# Connector_EEM.net
KiCad netlist of a schematic drawn in Altium Designer
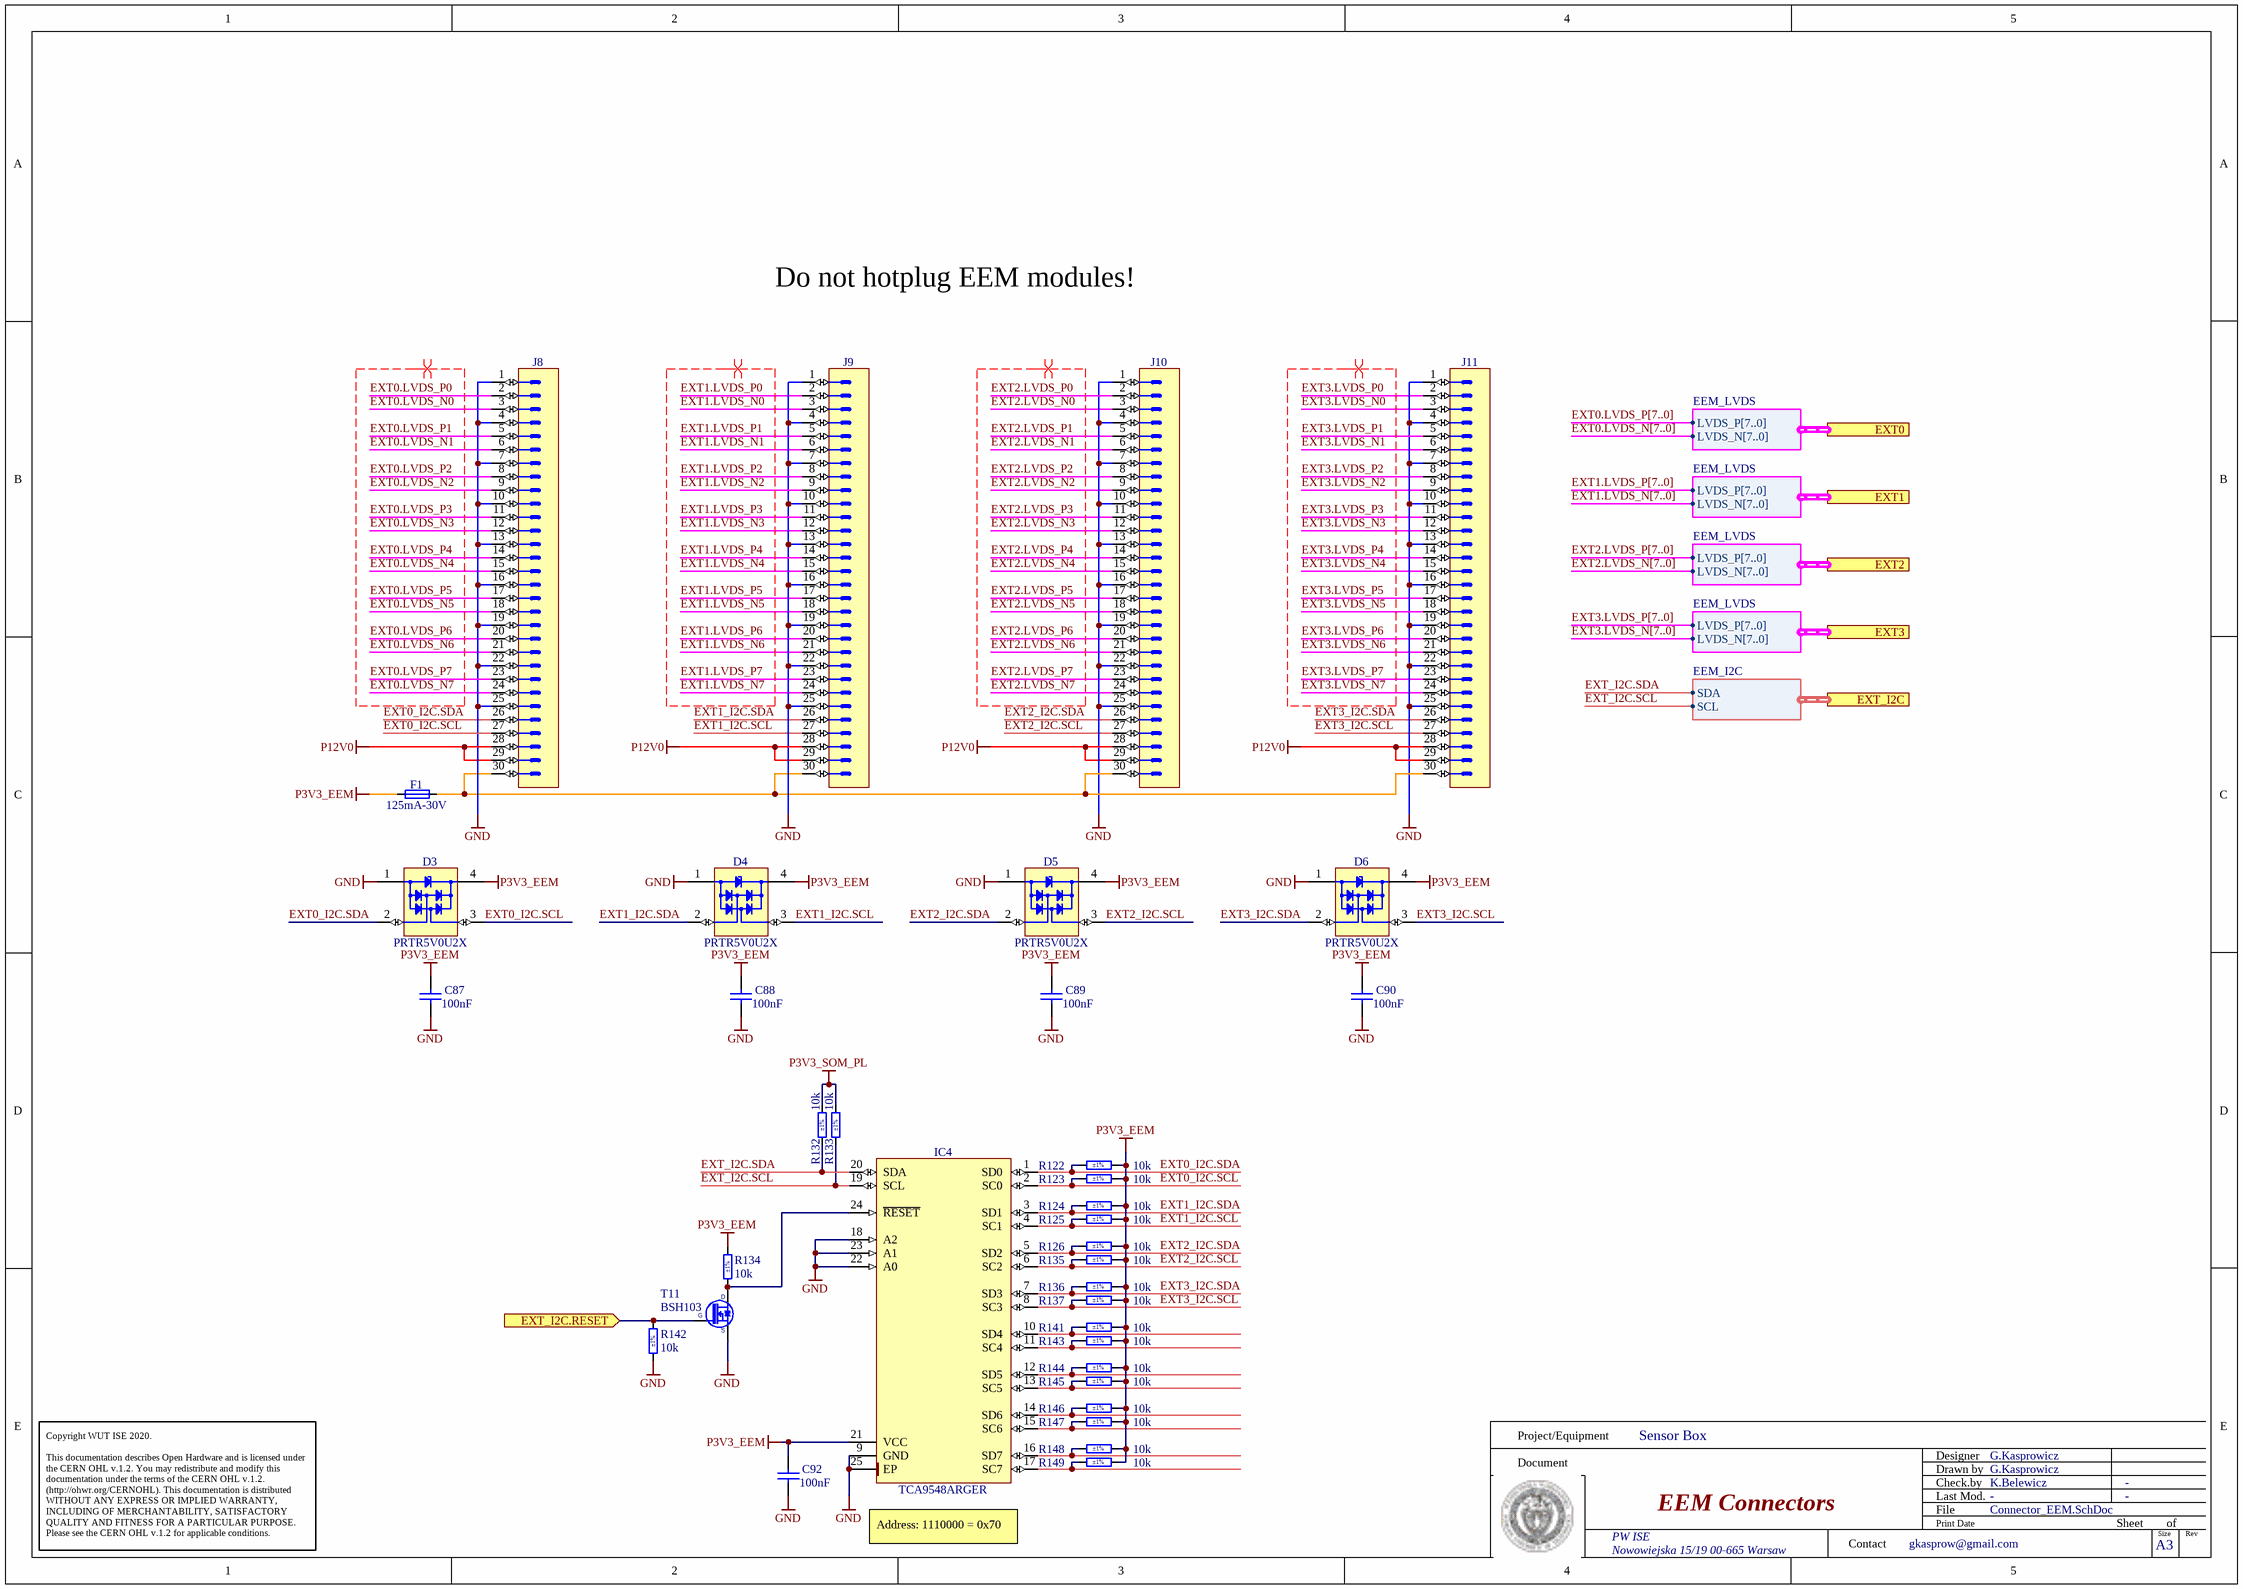
[diagram p0: Connector_EEM.SchDoc]

(export (version "E")
  (design (tool "Eeschema 10.0.6"))
  (components
    (comp (ref "C87")
      (value "100nF")
      (footprint "CAPC1005X55N")
      (description "Non-polarised capacitor")
      (fields
        (field (name "PART NUMBER") "CC0402_100NF_16V_10%_X5R")
        (field (name "VOLTAGE") "16V")
        (field (name "AUTHOR") "CERN DEM JLC")
      )
      (libsource (lib "Capacitors") (part "Capacitor - non polarized"))
    )
    (comp (ref "C88")
      (value "100nF")
      (footprint "CAPC1005X55N")
      (description "Non-polarised capacitor")
      (fields
        (field (name "PART NUMBER") "CC0402_100NF_16V_10%_X5R")
        (field (name "VOLTAGE") "16V")
        (field (name "AUTHOR") "CERN DEM JLC")
      )
      (libsource (lib "Capacitors") (part "Capacitor - non polarized"))
    )
    (comp (ref "C89")
      (value "100nF")
      (footprint "CAPC1005X55N")
      (description "Non-polarised capacitor")
      (fields
        (field (name "PART NUMBER") "CC0402_100NF_16V_10%_X5R")
        (field (name "VOLTAGE") "16V")
        (field (name "AUTHOR") "CERN DEM JLC")
      )
      (libsource (lib "Capacitors") (part "Capacitor - non polarized"))
    )
    (comp (ref "C90")
      (value "100nF")
      (footprint "CAPC1005X55N")
      (description "Non-polarised capacitor")
      (fields
        (field (name "PART NUMBER") "CC0402_100NF_16V_10%_X5R")
        (field (name "VOLTAGE") "16V")
        (field (name "AUTHOR") "CERN DEM JLC")
      )
      (libsource (lib "Capacitors") (part "Capacitor - non polarized"))
    )
    (comp (ref "C92")
      (value "100nF")
      (footprint "CAPC1005X55N")
      (description "Non-polarised capacitor")
      (fields
        (field (name "PART NUMBER") "CC0402_100NF_16V_10%_X5R")
        (field (name "VOLTAGE") "16V")
        (field (name "AUTHOR") "CERN DEM JLC")
      )
      (libsource (lib "Capacitors") (part "Capacitor - non polarized"))
    )
    (comp (ref "D3")
      (value "PRTR5V0U2X")
      (footprint "SOT190P230X110-4N")
      (description "Ultra Low Capacitance Double Rail-to-Rail ESD Protection Diode")
      (fields
        (field (name "VOLTAGE") "5.5V")
        (field (name "MANUFACTURER") "NXP SEMICONDUCTORS")
        (field (name "AUTHOR") "CERN DEM JLC")
      )
      (libsource (lib "ICs And Semiconductors") (part "PRTR5V0U2X"))
    )
    (comp (ref "D4")
      (value "PRTR5V0U2X")
      (footprint "SOT190P230X110-4N")
      (description "Ultra Low Capacitance Double Rail-to-Rail ESD Protection Diode")
      (fields
        (field (name "VOLTAGE") "5.5V")
        (field (name "MANUFACTURER") "NXP SEMICONDUCTORS")
        (field (name "AUTHOR") "CERN DEM JLC")
      )
      (libsource (lib "ICs And Semiconductors") (part "PRTR5V0U2X"))
    )
    (comp (ref "D5")
      (value "PRTR5V0U2X")
      (footprint "SOT190P230X110-4N")
      (description "Ultra Low Capacitance Double Rail-to-Rail ESD Protection Diode")
      (fields
        (field (name "VOLTAGE") "5.5V")
        (field (name "MANUFACTURER") "NXP SEMICONDUCTORS")
        (field (name "AUTHOR") "CERN DEM JLC")
      )
      (libsource (lib "ICs And Semiconductors") (part "PRTR5V0U2X"))
    )
    (comp (ref "D6")
      (value "PRTR5V0U2X")
      (footprint "SOT190P230X110-4N")
      (description "Ultra Low Capacitance Double Rail-to-Rail ESD Protection Diode")
      (fields
        (field (name "VOLTAGE") "5.5V")
        (field (name "MANUFACTURER") "NXP SEMICONDUCTORS")
        (field (name "AUTHOR") "CERN DEM JLC")
      )
      (libsource (lib "ICs And Semiconductors") (part "PRTR5V0U2X"))
    )
    (comp (ref "F1")
      (value "125mA-30V")
      (footprint "FUSR_LITTELFUSE_1206L012")
      (description "Fuse")
      (fields
        (field (name "PART NUMBER") "FUSR_LITTELFUSE_1206L012")
        (field (name "MANUFACTURER") "LITTELFUSE")
        (field (name "AUTHOR") "CERN DEM JLC")
      )
      (libsource (lib "Eletro-mechanical") (part "Fuse"))
    )
    (comp (ref "IC4")
      (value "TCA9548ARGER")
      (footprint "QFN50P400X400X100-25N-S220")
      (description "Low Voltage 8-Channel I2C Switch With Reset")
      (fields (field (name "MANUFACTURER") "TEXAS INSTRUMENTS") (field (name "AUTHOR") "CERN DEM JLC"))
      (libsource (lib "ICs And Semiconductors") (part "TCA9548ARGER"))
    )
    (comp (ref "J8")
      (value "~")
      (footprint "3M_N2530-6002RB")
      (description "Connector 30 Male")
      (fields
        (field (name "PART NUMBER") "3M_N2530-6002RB")
        (field (name "MANUFACTURER") "3M")
        (field (name "AUTHOR") "CERN DEM JLC")
      )
      (libsource (lib "Connectors") (part "Connector 30 Male"))
    )
    (comp (ref "J9")
      (value "~")
      (footprint "3M_N2530-6002RB")
      (description "Connector 30 Male")
      (fields
        (field (name "PART NUMBER") "3M_N2530-6002RB")
        (field (name "MANUFACTURER") "3M")
        (field (name "AUTHOR") "CERN DEM JLC")
      )
      (libsource (lib "Connectors") (part "Connector 30 Male"))
    )
    (comp (ref "J10")
      (value "~")
      (footprint "3M_N2530-6002RB")
      (description "Connector 30 Male")
      (fields
        (field (name "PART NUMBER") "3M_N2530-6002RB")
        (field (name "MANUFACTURER") "3M")
        (field (name "AUTHOR") "CERN DEM JLC")
      )
      (libsource (lib "Connectors") (part "Connector 30 Male"))
    )
    (comp (ref "J11")
      (value "~")
      (footprint "3M_N2530-6002RB")
      (description "Connector 30 Male")
      (fields
        (field (name "PART NUMBER") "3M_N2530-6002RB")
        (field (name "MANUFACTURER") "3M")
        (field (name "AUTHOR") "CERN DEM JLC")
      )
      (libsource (lib "Connectors") (part "Connector 30 Male"))
    )
    (comp (ref "R122")
      (value "10k")
      (footprint "RESC1005X40N")
      (description "Resistor - 1%")
      (fields
        (field (name "TOLERANCE") "±1%")
        (field (name "PART NUMBER") "R0402_10K_1%_0.0625W_100PPM")
        (field (name "POWER") "0.0625W")
        (field (name "AUTHOR") "CERN DEM JLC")
      )
      (libsource (lib "Resistors") (part "Resistor - 1%"))
    )
    (comp (ref "R123")
      (value "10k")
      (footprint "RESC1005X40N")
      (description "Resistor - 1%")
      (fields
        (field (name "TOLERANCE") "±1%")
        (field (name "PART NUMBER") "R0402_10K_1%_0.0625W_100PPM")
        (field (name "POWER") "0.0625W")
        (field (name "AUTHOR") "CERN DEM JLC")
      )
      (libsource (lib "Resistors") (part "Resistor - 1%"))
    )
    (comp (ref "R124")
      (value "10k")
      (footprint "RESC1005X40N")
      (description "Resistor - 1%")
      (fields
        (field (name "TOLERANCE") "±1%")
        (field (name "PART NUMBER") "R0402_10K_1%_0.0625W_100PPM")
        (field (name "POWER") "0.0625W")
        (field (name "AUTHOR") "CERN DEM JLC")
      )
      (libsource (lib "Resistors") (part "Resistor - 1%"))
    )
    (comp (ref "R125")
      (value "10k")
      (footprint "RESC1005X40N")
      (description "Resistor - 1%")
      (fields
        (field (name "TOLERANCE") "±1%")
        (field (name "PART NUMBER") "R0402_10K_1%_0.0625W_100PPM")
        (field (name "POWER") "0.0625W")
        (field (name "AUTHOR") "CERN DEM JLC")
      )
      (libsource (lib "Resistors") (part "Resistor - 1%"))
    )
    (comp (ref "R126")
      (value "10k")
      (footprint "RESC1005X40N")
      (description "Resistor - 1%")
      (fields
        (field (name "TOLERANCE") "±1%")
        (field (name "PART NUMBER") "R0402_10K_1%_0.0625W_100PPM")
        (field (name "POWER") "0.0625W")
        (field (name "AUTHOR") "CERN DEM JLC")
      )
      (libsource (lib "Resistors") (part "Resistor - 1%"))
    )
    (comp (ref "R132")
      (value "10k")
      (footprint "RESC1005X40N")
      (description "Resistor - 1%")
      (fields
        (field (name "TOLERANCE") "±1%")
        (field (name "PART NUMBER") "R0402_10K_1%_0.0625W_100PPM")
        (field (name "POWER") "0.0625W")
        (field (name "AUTHOR") "CERN DEM JLC")
      )
      (libsource (lib "Resistors") (part "Resistor - 1%"))
    )
    (comp (ref "R133")
      (value "10k")
      (footprint "RESC1005X40N")
      (description "Resistor - 1%")
      (fields
        (field (name "TOLERANCE") "±1%")
        (field (name "PART NUMBER") "R0402_10K_1%_0.0625W_100PPM")
        (field (name "POWER") "0.0625W")
        (field (name "AUTHOR") "CERN DEM JLC")
      )
      (libsource (lib "Resistors") (part "Resistor - 1%"))
    )
    (comp (ref "R134")
      (value "10k")
      (footprint "RESC1005X40N")
      (description "Resistor - 1%")
      (fields
        (field (name "TOLERANCE") "±1%")
        (field (name "PART NUMBER") "R0402_10K_1%_0.0625W_100PPM")
        (field (name "POWER") "0.0625W")
        (field (name "AUTHOR") "CERN DEM JLC")
      )
      (libsource (lib "Resistors") (part "Resistor - 1%"))
    )
    (comp (ref "R135")
      (value "10k")
      (footprint "RESC1005X40N")
      (description "Resistor - 1%")
      (fields
        (field (name "TOLERANCE") "±1%")
        (field (name "PART NUMBER") "R0402_10K_1%_0.0625W_100PPM")
        (field (name "POWER") "0.0625W")
        (field (name "AUTHOR") "CERN DEM JLC")
      )
      (libsource (lib "Resistors") (part "Resistor - 1%"))
    )
    (comp (ref "R136")
      (value "10k")
      (footprint "RESC1005X40N")
      (description "Resistor - 1%")
      (fields
        (field (name "TOLERANCE") "±1%")
        (field (name "PART NUMBER") "R0402_10K_1%_0.0625W_100PPM")
        (field (name "POWER") "0.0625W")
        (field (name "AUTHOR") "CERN DEM JLC")
      )
      (libsource (lib "Resistors") (part "Resistor - 1%"))
    )
    (comp (ref "R137")
      (value "10k")
      (footprint "RESC1005X40N")
      (description "Resistor - 1%")
      (fields
        (field (name "TOLERANCE") "±1%")
        (field (name "PART NUMBER") "R0402_10K_1%_0.0625W_100PPM")
        (field (name "POWER") "0.0625W")
        (field (name "AUTHOR") "CERN DEM JLC")
      )
      (libsource (lib "Resistors") (part "Resistor - 1%"))
    )
    (comp (ref "R141")
      (value "10k")
      (footprint "RESC1005X40N")
      (description "Resistor - 1%")
      (fields
        (field (name "TOLERANCE") "±1%")
        (field (name "PART NUMBER") "R0402_10K_1%_0.0625W_100PPM")
        (field (name "POWER") "0.0625W")
        (field (name "AUTHOR") "CERN DEM JLC")
      )
      (libsource (lib "Resistors") (part "Resistor - 1%"))
    )
    (comp (ref "R142")
      (value "10k")
      (footprint "RESC1005X40N")
      (description "Resistor - 1%")
      (fields
        (field (name "TOLERANCE") "±1%")
        (field (name "PART NUMBER") "R0402_10K_1%_0.0625W_100PPM")
        (field (name "POWER") "0.0625W")
        (field (name "AUTHOR") "CERN DEM JLC")
      )
      (libsource (lib "Resistors") (part "Resistor - 1%"))
    )
    (comp (ref "R143")
      (value "10k")
      (footprint "RESC1005X40N")
      (description "Resistor - 1%")
      (fields
        (field (name "TOLERANCE") "±1%")
        (field (name "PART NUMBER") "R0402_10K_1%_0.0625W_100PPM")
        (field (name "POWER") "0.0625W")
        (field (name "AUTHOR") "CERN DEM JLC")
      )
      (libsource (lib "Resistors") (part "Resistor - 1%"))
    )
    (comp (ref "R144")
      (value "10k")
      (footprint "RESC1005X40N")
      (description "Resistor - 1%")
      (fields
        (field (name "TOLERANCE") "±1%")
        (field (name "PART NUMBER") "R0402_10K_1%_0.0625W_100PPM")
        (field (name "POWER") "0.0625W")
        (field (name "AUTHOR") "CERN DEM JLC")
      )
      (libsource (lib "Resistors") (part "Resistor - 1%"))
    )
    (comp (ref "R145")
      (value "10k")
      (footprint "RESC1005X40N")
      (description "Resistor - 1%")
      (fields
        (field (name "TOLERANCE") "±1%")
        (field (name "PART NUMBER") "R0402_10K_1%_0.0625W_100PPM")
        (field (name "POWER") "0.0625W")
        (field (name "AUTHOR") "CERN DEM JLC")
      )
      (libsource (lib "Resistors") (part "Resistor - 1%"))
    )
    (comp (ref "R146")
      (value "10k")
      (footprint "RESC1005X40N")
      (description "Resistor - 1%")
      (fields
        (field (name "TOLERANCE") "±1%")
        (field (name "PART NUMBER") "R0402_10K_1%_0.0625W_100PPM")
        (field (name "POWER") "0.0625W")
        (field (name "AUTHOR") "CERN DEM JLC")
      )
      (libsource (lib "Resistors") (part "Resistor - 1%"))
    )
    (comp (ref "R147")
      (value "10k")
      (footprint "RESC1005X40N")
      (description "Resistor - 1%")
      (fields
        (field (name "TOLERANCE") "±1%")
        (field (name "PART NUMBER") "R0402_10K_1%_0.0625W_100PPM")
        (field (name "POWER") "0.0625W")
        (field (name "AUTHOR") "CERN DEM JLC")
      )
      (libsource (lib "Resistors") (part "Resistor - 1%"))
    )
    (comp (ref "R148")
      (value "10k")
      (footprint "RESC1005X40N")
      (description "Resistor - 1%")
      (fields
        (field (name "TOLERANCE") "±1%")
        (field (name "PART NUMBER") "R0402_10K_1%_0.0625W_100PPM")
        (field (name "POWER") "0.0625W")
        (field (name "AUTHOR") "CERN DEM JLC")
      )
      (libsource (lib "Resistors") (part "Resistor - 1%"))
    )
    (comp (ref "R149")
      (value "10k")
      (footprint "RESC1005X40N")
      (description "Resistor - 1%")
      (fields
        (field (name "TOLERANCE") "±1%")
        (field (name "PART NUMBER") "R0402_10K_1%_0.0625W_100PPM")
        (field (name "POWER") "0.0625W")
        (field (name "AUTHOR") "CERN DEM JLC")
      )
      (libsource (lib "Resistors") (part "Resistor - 1%"))
    )
    (comp (ref "T11")
      (value "BSH103")
      (footprint "SOT95P230X110-3N")
      (description "N-CHANNEL MOSFET WITH DIODE")
      (fields (field (name "MANUFACTURER") "NEXPERIA") (field (name "AUTHOR") "CERN DEM JLC"))
      (libsource (lib "ICs And Semiconductors") (part "N-MOSFET-D 1G 2S 3D"))
    )
  )
  (nets
    (net (code "3") (name "/EXT0.LVDS_N0") (class "Default")
      (node (ref "J8") (pin "3") (pinfunction "3_3") (pintype "bidirectional"))
    )
    (net (code "4") (name "/EXT0.LVDS_N1") (class "Default")
      (node (ref "J8") (pin "6") (pinfunction "6_6") (pintype "bidirectional"))
    )
    (net (code "5") (name "/EXT0.LVDS_N2") (class "Default")
      (node (ref "J8") (pin "9") (pinfunction "9_9") (pintype "bidirectional"))
    )
    (net (code "6") (name "/EXT0.LVDS_N3") (class "Default")
      (node (ref "J8") (pin "12") (pinfunction "12_12") (pintype "bidirectional"))
    )
    (net (code "7") (name "/EXT0.LVDS_N4") (class "Default")
      (node (ref "J8") (pin "15") (pinfunction "15_15") (pintype "bidirectional"))
    )
    (net (code "8") (name "/EXT0.LVDS_N5") (class "Default")
      (node (ref "J8") (pin "18") (pinfunction "18_18") (pintype "bidirectional"))
    )
    (net (code "9") (name "/EXT0.LVDS_N6") (class "Default")
      (node (ref "J8") (pin "21") (pinfunction "21_21") (pintype "bidirectional"))
    )
    (net (code "10") (name "/EXT0.LVDS_N7") (class "Default")
      (node (ref "J8") (pin "24") (pinfunction "24_24") (pintype "bidirectional"))
    )
    (net (code "12") (name "/EXT0.LVDS_P0") (class "Default")
      (node (ref "J8") (pin "2") (pinfunction "2_2") (pintype "bidirectional"))
    )
    (net (code "13") (name "/EXT0.LVDS_P1") (class "Default")
      (node (ref "J8") (pin "5") (pinfunction "5_5") (pintype "bidirectional"))
    )
    (net (code "14") (name "/EXT0.LVDS_P2") (class "Default")
      (node (ref "J8") (pin "8") (pinfunction "8_8") (pintype "bidirectional"))
    )
    (net (code "15") (name "/EXT0.LVDS_P3") (class "Default")
      (node (ref "J8") (pin "11") (pinfunction "11_11") (pintype "bidirectional"))
    )
    (net (code "16") (name "/EXT0.LVDS_P4") (class "Default")
      (node (ref "J8") (pin "14") (pinfunction "14_14") (pintype "bidirectional"))
    )
    (net (code "17") (name "/EXT0.LVDS_P5") (class "Default")
      (node (ref "J8") (pin "17") (pinfunction "17_17") (pintype "bidirectional"))
    )
    (net (code "18") (name "/EXT0.LVDS_P6") (class "Default")
      (node (ref "J8") (pin "20") (pinfunction "20_20") (pintype "bidirectional"))
    )
    (net (code "19") (name "/EXT0.LVDS_P7") (class "Default")
      (node (ref "J8") (pin "23") (pinfunction "23_23") (pintype "bidirectional"))
    )
    (net (code "21") (name "/EXT0_I2C.SCL") (class "Default")
      (node (ref "D3") (pin "3") (pinfunction "I/O2_3") (pintype "bidirectional"))
      (node (ref "IC4") (pin "2") (pinfunction "SC0_2") (pintype "bidirectional"))
      (node (ref "J8") (pin "27") (pinfunction "27_27") (pintype "bidirectional"))
      (node (ref "R123") (pin "1") (pinfunction "1_1") (pintype "passive"))
    )
    (net (code "22") (name "/EXT0_I2C.SDA") (class "Default")
      (node (ref "D3") (pin "2") (pinfunction "I/O1_2") (pintype "bidirectional"))
      (node (ref "IC4") (pin "1") (pinfunction "SD0_1") (pintype "bidirectional"))
      (node (ref "J8") (pin "26") (pinfunction "26_26") (pintype "bidirectional"))
      (node (ref "R122") (pin "1") (pinfunction "1_1") (pintype "passive"))
    )
    (net (code "23") (name "/EXT1.LVDS_N0") (class "Default")
      (node (ref "J9") (pin "3") (pinfunction "3_3") (pintype "bidirectional"))
    )
    (net (code "24") (name "/EXT1.LVDS_N1") (class "Default")
      (node (ref "J9") (pin "6") (pinfunction "6_6") (pintype "bidirectional"))
    )
    (net (code "25") (name "/EXT1.LVDS_N2") (class "Default")
      (node (ref "J9") (pin "9") (pinfunction "9_9") (pintype "bidirectional"))
    )
    (net (code "26") (name "/EXT1.LVDS_N3") (class "Default")
      (node (ref "J9") (pin "12") (pinfunction "12_12") (pintype "bidirectional"))
    )
    (net (code "27") (name "/EXT1.LVDS_N4") (class "Default")
      (node (ref "J9") (pin "15") (pinfunction "15_15") (pintype "bidirectional"))
    )
    (net (code "28") (name "/EXT1.LVDS_N5") (class "Default")
      (node (ref "J9") (pin "18") (pinfunction "18_18") (pintype "bidirectional"))
    )
    (net (code "29") (name "/EXT1.LVDS_N6") (class "Default")
      (node (ref "J9") (pin "21") (pinfunction "21_21") (pintype "bidirectional"))
    )
    (net (code "30") (name "/EXT1.LVDS_N7") (class "Default")
      (node (ref "J9") (pin "24") (pinfunction "24_24") (pintype "bidirectional"))
    )
    (net (code "32") (name "/EXT1.LVDS_P0") (class "Default")
      (node (ref "J9") (pin "2") (pinfunction "2_2") (pintype "bidirectional"))
    )
    (net (code "33") (name "/EXT1.LVDS_P1") (class "Default")
      (node (ref "J9") (pin "5") (pinfunction "5_5") (pintype "bidirectional"))
    )
    (net (code "34") (name "/EXT1.LVDS_P2") (class "Default")
      (node (ref "J9") (pin "8") (pinfunction "8_8") (pintype "bidirectional"))
    )
    (net (code "35") (name "/EXT1.LVDS_P3") (class "Default")
      (node (ref "J9") (pin "11") (pinfunction "11_11") (pintype "bidirectional"))
    )
    (net (code "36") (name "/EXT1.LVDS_P4") (class "Default")
      (node (ref "J9") (pin "14") (pinfunction "14_14") (pintype "bidirectional"))
    )
    (net (code "37") (name "/EXT1.LVDS_P5") (class "Default")
      (node (ref "J9") (pin "17") (pinfunction "17_17") (pintype "bidirectional"))
    )
    (net (code "38") (name "/EXT1.LVDS_P6") (class "Default")
      (node (ref "J9") (pin "20") (pinfunction "20_20") (pintype "bidirectional"))
    )
    (net (code "39") (name "/EXT1.LVDS_P7") (class "Default")
      (node (ref "J9") (pin "23") (pinfunction "23_23") (pintype "bidirectional"))
    )
    (net (code "41") (name "/EXT1_I2C.SCL") (class "Default")
      (node (ref "D4") (pin "3") (pinfunction "I/O2_3") (pintype "bidirectional"))
      (node (ref "IC4") (pin "4") (pinfunction "SC1_4") (pintype "bidirectional"))
      (node (ref "J9") (pin "27") (pinfunction "27_27") (pintype "bidirectional"))
      (node (ref "R125") (pin "1") (pinfunction "1_1") (pintype "passive"))
    )
    (net (code "42") (name "/EXT1_I2C.SDA") (class "Default")
      (node (ref "D4") (pin "2") (pinfunction "I/O1_2") (pintype "bidirectional"))
      (node (ref "IC4") (pin "3") (pinfunction "SD1_3") (pintype "bidirectional"))
      (node (ref "J9") (pin "26") (pinfunction "26_26") (pintype "bidirectional"))
      (node (ref "R124") (pin "1") (pinfunction "1_1") (pintype "passive"))
    )
    (net (code "43") (name "/EXT2.LVDS_N0") (class "Default")
      (node (ref "J10") (pin "3") (pinfunction "3_3") (pintype "bidirectional"))
    )
    (net (code "44") (name "/EXT2.LVDS_N1") (class "Default")
      (node (ref "J10") (pin "6") (pinfunction "6_6") (pintype "bidirectional"))
    )
    (net (code "45") (name "/EXT2.LVDS_N2") (class "Default")
      (node (ref "J10") (pin "9") (pinfunction "9_9") (pintype "bidirectional"))
    )
    (net (code "46") (name "/EXT2.LVDS_N3") (class "Default")
      (node (ref "J10") (pin "12") (pinfunction "12_12") (pintype "bidirectional"))
    )
    (net (code "47") (name "/EXT2.LVDS_N4") (class "Default")
      (node (ref "J10") (pin "15") (pinfunction "15_15") (pintype "bidirectional"))
    )
    (net (code "48") (name "/EXT2.LVDS_N5") (class "Default")
      (node (ref "J10") (pin "18") (pinfunction "18_18") (pintype "bidirectional"))
    )
    (net (code "49") (name "/EXT2.LVDS_N6") (class "Default")
      (node (ref "J10") (pin "21") (pinfunction "21_21") (pintype "bidirectional"))
    )
    (net (code "50") (name "/EXT2.LVDS_N7") (class "Default")
      (node (ref "J10") (pin "24") (pinfunction "24_24") (pintype "bidirectional"))
    )
    (net (code "52") (name "/EXT2.LVDS_P0") (class "Default")
      (node (ref "J10") (pin "2") (pinfunction "2_2") (pintype "bidirectional"))
    )
    (net (code "53") (name "/EXT2.LVDS_P1") (class "Default")
      (node (ref "J10") (pin "5") (pinfunction "5_5") (pintype "bidirectional"))
    )
    (net (code "54") (name "/EXT2.LVDS_P2") (class "Default")
      (node (ref "J10") (pin "8") (pinfunction "8_8") (pintype "bidirectional"))
    )
    (net (code "55") (name "/EXT2.LVDS_P3") (class "Default")
      (node (ref "J10") (pin "11") (pinfunction "11_11") (pintype "bidirectional"))
    )
    (net (code "56") (name "/EXT2.LVDS_P4") (class "Default")
      (node (ref "J10") (pin "14") (pinfunction "14_14") (pintype "bidirectional"))
    )
    (net (code "57") (name "/EXT2.LVDS_P5") (class "Default")
      (node (ref "J10") (pin "17") (pinfunction "17_17") (pintype "bidirectional"))
    )
    (net (code "58") (name "/EXT2.LVDS_P6") (class "Default")
      (node (ref "J10") (pin "20") (pinfunction "20_20") (pintype "bidirectional"))
    )
    (net (code "59") (name "/EXT2.LVDS_P7") (class "Default")
      (node (ref "J10") (pin "23") (pinfunction "23_23") (pintype "bidirectional"))
    )
    (net (code "61") (name "/EXT2_I2C.SCL") (class "Default")
      (node (ref "D5") (pin "3") (pinfunction "I/O2_3") (pintype "bidirectional"))
      (node (ref "IC4") (pin "6") (pinfunction "SC2_6") (pintype "bidirectional"))
      (node (ref "J10") (pin "27") (pinfunction "27_27") (pintype "bidirectional"))
      (node (ref "R135") (pin "1") (pinfunction "1_1") (pintype "passive"))
    )
    (net (code "62") (name "/EXT2_I2C.SDA") (class "Default")
      (node (ref "D5") (pin "2") (pinfunction "I/O1_2") (pintype "bidirectional"))
      (node (ref "IC4") (pin "5") (pinfunction "SD2_5") (pintype "bidirectional"))
      (node (ref "J10") (pin "26") (pinfunction "26_26") (pintype "bidirectional"))
      (node (ref "R126") (pin "1") (pinfunction "1_1") (pintype "passive"))
    )
    (net (code "63") (name "/EXT3.LVDS_N0") (class "Default")
      (node (ref "J11") (pin "3") (pinfunction "3_3") (pintype "bidirectional"))
    )
    (net (code "64") (name "/EXT3.LVDS_N1") (class "Default")
      (node (ref "J11") (pin "6") (pinfunction "6_6") (pintype "bidirectional"))
    )
    (net (code "65") (name "/EXT3.LVDS_N2") (class "Default")
      (node (ref "J11") (pin "9") (pinfunction "9_9") (pintype "bidirectional"))
    )
    (net (code "66") (name "/EXT3.LVDS_N3") (class "Default")
      (node (ref "J11") (pin "12") (pinfunction "12_12") (pintype "bidirectional"))
    )
    (net (code "67") (name "/EXT3.LVDS_N4") (class "Default")
      (node (ref "J11") (pin "15") (pinfunction "15_15") (pintype "bidirectional"))
    )
    (net (code "68") (name "/EXT3.LVDS_N5") (class "Default")
      (node (ref "J11") (pin "18") (pinfunction "18_18") (pintype "bidirectional"))
    )
    (net (code "69") (name "/EXT3.LVDS_N6") (class "Default")
      (node (ref "J11") (pin "21") (pinfunction "21_21") (pintype "bidirectional"))
    )
    (net (code "70") (name "/EXT3.LVDS_N7") (class "Default")
      (node (ref "J11") (pin "24") (pinfunction "24_24") (pintype "bidirectional"))
    )
    (net (code "72") (name "/EXT3.LVDS_P0") (class "Default")
      (node (ref "J11") (pin "2") (pinfunction "2_2") (pintype "bidirectional"))
    )
    (net (code "73") (name "/EXT3.LVDS_P1") (class "Default")
      (node (ref "J11") (pin "5") (pinfunction "5_5") (pintype "bidirectional"))
    )
    (net (code "74") (name "/EXT3.LVDS_P2") (class "Default")
      (node (ref "J11") (pin "8") (pinfunction "8_8") (pintype "bidirectional"))
    )
    (net (code "75") (name "/EXT3.LVDS_P3") (class "Default")
      (node (ref "J11") (pin "11") (pinfunction "11_11") (pintype "bidirectional"))
    )
    (net (code "76") (name "/EXT3.LVDS_P4") (class "Default")
      (node (ref "J11") (pin "14") (pinfunction "14_14") (pintype "bidirectional"))
    )
    (net (code "77") (name "/EXT3.LVDS_P5") (class "Default")
      (node (ref "J11") (pin "17") (pinfunction "17_17") (pintype "bidirectional"))
    )
    (net (code "78") (name "/EXT3.LVDS_P6") (class "Default")
      (node (ref "J11") (pin "20") (pinfunction "20_20") (pintype "bidirectional"))
    )
    (net (code "79") (name "/EXT3.LVDS_P7") (class "Default")
      (node (ref "J11") (pin "23") (pinfunction "23_23") (pintype "bidirectional"))
    )
    (net (code "81") (name "/EXT3_I2C.SCL") (class "Default")
      (node (ref "D6") (pin "3") (pinfunction "I/O2_3") (pintype "bidirectional"))
      (node (ref "IC4") (pin "8") (pinfunction "SC3_8") (pintype "bidirectional"))
      (node (ref "J11") (pin "27") (pinfunction "27_27") (pintype "bidirectional"))
      (node (ref "R137") (pin "1") (pinfunction "1_1") (pintype "passive"))
    )
    (net (code "82") (name "/EXT3_I2C.SDA") (class "Default")
      (node (ref "D6") (pin "2") (pinfunction "I/O1_2") (pintype "bidirectional"))
      (node (ref "IC4") (pin "7") (pinfunction "SD3_7") (pintype "bidirectional"))
      (node (ref "J11") (pin "26") (pinfunction "26_26") (pintype "bidirectional"))
      (node (ref "R136") (pin "1") (pinfunction "1_1") (pintype "passive"))
    )
    (net (code "83") (name "/EXT_I2C.RESET") (class "Default")
      (node (ref "R142") (pin "2") (pinfunction "2_2") (pintype "passive"))
      (node (ref "T11") (pin "1") (pinfunction "G_1") (pintype "passive"))
    )
    (net (code "84") (name "/EXT_I2C.SCL") (class "Default")
      (node (ref "IC4") (pin "19") (pinfunction "SCL_19") (pintype "bidirectional"))
      (node (ref "R133") (pin "1") (pinfunction "1_1") (pintype "passive"))
    )
    (net (code "85") (name "/EXT_I2C.SDA") (class "Default")
      (node (ref "IC4") (pin "20") (pinfunction "SDA_20") (pintype "bidirectional"))
      (node (ref "R132") (pin "1") (pinfunction "1_1") (pintype "passive"))
    )
    (net (code "88") (name "GND") (class "Default")
      (node (ref "C87") (pin "1") (pinfunction "1_1") (pintype "passive"))
      (node (ref "C88") (pin "1") (pinfunction "1_1") (pintype "passive"))
      (node (ref "C89") (pin "1") (pinfunction "1_1") (pintype "passive"))
      (node (ref "C90") (pin "1") (pinfunction "1_1") (pintype "passive"))
      (node (ref "C92") (pin "1") (pinfunction "1_1") (pintype "passive"))
      (node (ref "D3") (pin "1") (pinfunction "GND_1") (pintype "power_in"))
      (node (ref "D4") (pin "1") (pinfunction "GND_1") (pintype "power_in"))
      (node (ref "D5") (pin "1") (pinfunction "GND_1") (pintype "power_in"))
      (node (ref "D6") (pin "1") (pinfunction "GND_1") (pintype "power_in"))
      (node (ref "IC4") (pin "18") (pinfunction "A2_18") (pintype "input"))
      (node (ref "IC4") (pin "22") (pinfunction "A0_22") (pintype "input"))
      (node (ref "IC4") (pin "23") (pinfunction "A1_23") (pintype "input"))
      (node (ref "IC4") (pin "25") (pinfunction "EP_25") (pintype "power_in"))
      (node (ref "IC4") (pin "9") (pinfunction "GND_9") (pintype "power_in"))
      (node (ref "J10") (pin "1") (pinfunction "1_1") (pintype "bidirectional"))
      (node (ref "J10") (pin "10") (pinfunction "10_10") (pintype "bidirectional"))
      (node (ref "J10") (pin "13") (pinfunction "13_13") (pintype "bidirectional"))
      (node (ref "J10") (pin "16") (pinfunction "16_16") (pintype "bidirectional"))
      (node (ref "J10") (pin "19") (pinfunction "19_19") (pintype "bidirectional"))
      (node (ref "J10") (pin "22") (pinfunction "22_22") (pintype "bidirectional"))
      (node (ref "J10") (pin "25") (pinfunction "25_25") (pintype "bidirectional"))
      (node (ref "J10") (pin "4") (pinfunction "4_4") (pintype "bidirectional"))
      (node (ref "J10") (pin "7") (pinfunction "7_7") (pintype "bidirectional"))
      (node (ref "J11") (pin "1") (pinfunction "1_1") (pintype "bidirectional"))
      (node (ref "J11") (pin "10") (pinfunction "10_10") (pintype "bidirectional"))
      (node (ref "J11") (pin "13") (pinfunction "13_13") (pintype "bidirectional"))
      (node (ref "J11") (pin "16") (pinfunction "16_16") (pintype "bidirectional"))
      (node (ref "J11") (pin "19") (pinfunction "19_19") (pintype "bidirectional"))
      (node (ref "J11") (pin "22") (pinfunction "22_22") (pintype "bidirectional"))
      (node (ref "J11") (pin "25") (pinfunction "25_25") (pintype "bidirectional"))
      (node (ref "J11") (pin "4") (pinfunction "4_4") (pintype "bidirectional"))
      (node (ref "J11") (pin "7") (pinfunction "7_7") (pintype "bidirectional"))
      (node (ref "J8") (pin "1") (pinfunction "1_1") (pintype "bidirectional"))
      (node (ref "J8") (pin "10") (pinfunction "10_10") (pintype "bidirectional"))
      (node (ref "J8") (pin "13") (pinfunction "13_13") (pintype "bidirectional"))
      (node (ref "J8") (pin "16") (pinfunction "16_16") (pintype "bidirectional"))
      (node (ref "J8") (pin "19") (pinfunction "19_19") (pintype "bidirectional"))
      (node (ref "J8") (pin "22") (pinfunction "22_22") (pintype "bidirectional"))
      (node (ref "J8") (pin "25") (pinfunction "25_25") (pintype "bidirectional"))
      (node (ref "J8") (pin "4") (pinfunction "4_4") (pintype "bidirectional"))
      (node (ref "J8") (pin "7") (pinfunction "7_7") (pintype "bidirectional"))
      (node (ref "J9") (pin "1") (pinfunction "1_1") (pintype "bidirectional"))
      (node (ref "J9") (pin "10") (pinfunction "10_10") (pintype "bidirectional"))
      (node (ref "J9") (pin "13") (pinfunction "13_13") (pintype "bidirectional"))
      (node (ref "J9") (pin "16") (pinfunction "16_16") (pintype "bidirectional"))
      (node (ref "J9") (pin "19") (pinfunction "19_19") (pintype "bidirectional"))
      (node (ref "J9") (pin "22") (pinfunction "22_22") (pintype "bidirectional"))
      (node (ref "J9") (pin "25") (pinfunction "25_25") (pintype "bidirectional"))
      (node (ref "J9") (pin "4") (pinfunction "4_4") (pintype "bidirectional"))
      (node (ref "J9") (pin "7") (pinfunction "7_7") (pintype "bidirectional"))
      (node (ref "R142") (pin "1") (pinfunction "1_1") (pintype "passive"))
      (node (ref "T11") (pin "2") (pinfunction "S_2") (pintype "passive"))
    )
    (net (code "89") (name "Net-(F1-Pad2)") (class "Default")
      (node (ref "F1") (pin "2") (pinfunction "2_2") (pintype "passive"))
      (node (ref "J10") (pin "30") (pinfunction "30_30") (pintype "bidirectional"))
      (node (ref "J11") (pin "30") (pinfunction "30_30") (pintype "bidirectional"))
      (node (ref "J8") (pin "30") (pinfunction "30_30") (pintype "bidirectional"))
      (node (ref "J9") (pin "30") (pinfunction "30_30") (pintype "bidirectional"))
    )
    (net (code "90") (name "Net-(IC4-SC4)") (class "Default")
      (node (ref "IC4") (pin "11") (pinfunction "SC4_11") (pintype "bidirectional"))
      (node (ref "R143") (pin "1") (pinfunction "1_1") (pintype "passive"))
    )
    (net (code "91") (name "Net-(IC4-SC5)") (class "Default")
      (node (ref "IC4") (pin "13") (pinfunction "SC5_13") (pintype "bidirectional"))
      (node (ref "R145") (pin "1") (pinfunction "1_1") (pintype "passive"))
    )
    (net (code "92") (name "Net-(IC4-SC6)") (class "Default")
      (node (ref "IC4") (pin "15") (pinfunction "SC6_15") (pintype "bidirectional"))
      (node (ref "R147") (pin "1") (pinfunction "1_1") (pintype "passive"))
    )
    (net (code "93") (name "Net-(IC4-SC7)") (class "Default")
      (node (ref "IC4") (pin "17") (pinfunction "SC7_17") (pintype "bidirectional"))
      (node (ref "R149") (pin "1") (pinfunction "1_1") (pintype "passive"))
    )
    (net (code "94") (name "Net-(IC4-SD4)") (class "Default")
      (node (ref "IC4") (pin "10") (pinfunction "SD4_10") (pintype "bidirectional"))
      (node (ref "R141") (pin "1") (pinfunction "1_1") (pintype "passive"))
    )
    (net (code "95") (name "Net-(IC4-SD5)") (class "Default")
      (node (ref "IC4") (pin "12") (pinfunction "SD5_12") (pintype "bidirectional"))
      (node (ref "R144") (pin "1") (pinfunction "1_1") (pintype "passive"))
    )
    (net (code "96") (name "Net-(IC4-SD6)") (class "Default")
      (node (ref "IC4") (pin "14") (pinfunction "SD6_14") (pintype "bidirectional"))
      (node (ref "R146") (pin "1") (pinfunction "1_1") (pintype "passive"))
    )
    (net (code "97") (name "Net-(IC4-SD7)") (class "Default")
      (node (ref "IC4") (pin "16") (pinfunction "SD7_16") (pintype "bidirectional"))
      (node (ref "R148") (pin "1") (pinfunction "1_1") (pintype "passive"))
    )
    (net (code "98") (name "Net-(IC4-~{RESET})") (class "Default")
      (node (ref "IC4") (pin "24") (pinfunction "~{RESET}_24") (pintype "input"))
      (node (ref "R134") (pin "1") (pinfunction "1_1") (pintype "passive"))
      (node (ref "T11") (pin "3") (pinfunction "D_3") (pintype "passive"))
    )
    (net (code "99") (name "P3V3_EEM") (class "Default")
      (node (ref "C87") (pin "2") (pinfunction "2_2") (pintype "passive"))
      (node (ref "C88") (pin "2") (pinfunction "2_2") (pintype "passive"))
      (node (ref "C89") (pin "2") (pinfunction "2_2") (pintype "passive"))
      (node (ref "C90") (pin "2") (pinfunction "2_2") (pintype "passive"))
      (node (ref "C92") (pin "2") (pinfunction "2_2") (pintype "passive"))
      (node (ref "D3") (pin "4") (pinfunction "VCC_4") (pintype "power_in"))
      (node (ref "D4") (pin "4") (pinfunction "VCC_4") (pintype "power_in"))
      (node (ref "D5") (pin "4") (pinfunction "VCC_4") (pintype "power_in"))
      (node (ref "D6") (pin "4") (pinfunction "VCC_4") (pintype "power_in"))
      (node (ref "F1") (pin "1") (pinfunction "1_1") (pintype "passive"))
      (node (ref "IC4") (pin "21") (pinfunction "VCC_21") (pintype "power_in"))
      (node (ref "R122") (pin "2") (pinfunction "2_2") (pintype "passive"))
      (node (ref "R123") (pin "2") (pinfunction "2_2") (pintype "passive"))
      (node (ref "R124") (pin "2") (pinfunction "2_2") (pintype "passive"))
      (node (ref "R125") (pin "2") (pinfunction "2_2") (pintype "passive"))
      (node (ref "R126") (pin "2") (pinfunction "2_2") (pintype "passive"))
      (node (ref "R134") (pin "2") (pinfunction "2_2") (pintype "passive"))
      (node (ref "R135") (pin "2") (pinfunction "2_2") (pintype "passive"))
      (node (ref "R136") (pin "2") (pinfunction "2_2") (pintype "passive"))
      (node (ref "R137") (pin "2") (pinfunction "2_2") (pintype "passive"))
      (node (ref "R141") (pin "2") (pinfunction "2_2") (pintype "passive"))
      (node (ref "R143") (pin "2") (pinfunction "2_2") (pintype "passive"))
      (node (ref "R144") (pin "2") (pinfunction "2_2") (pintype "passive"))
      (node (ref "R145") (pin "2") (pinfunction "2_2") (pintype "passive"))
      (node (ref "R146") (pin "2") (pinfunction "2_2") (pintype "passive"))
      (node (ref "R147") (pin "2") (pinfunction "2_2") (pintype "passive"))
      (node (ref "R148") (pin "2") (pinfunction "2_2") (pintype "passive"))
      (node (ref "R149") (pin "2") (pinfunction "2_2") (pintype "passive"))
    )
    (net (code "100") (name "P3V3_SOM_PL") (class "Default")
      (node (ref "R132") (pin "2") (pinfunction "2_2") (pintype "passive"))
      (node (ref "R133") (pin "2") (pinfunction "2_2") (pintype "passive"))
    )
    (net (code "101") (name "P12V0") (class "Default")
      (node (ref "J10") (pin "28") (pinfunction "28_28") (pintype "bidirectional"))
      (node (ref "J10") (pin "29") (pinfunction "29_29") (pintype "bidirectional"))
      (node (ref "J11") (pin "28") (pinfunction "28_28") (pintype "bidirectional"))
      (node (ref "J11") (pin "29") (pinfunction "29_29") (pintype "bidirectional"))
      (node (ref "J8") (pin "28") (pinfunction "28_28") (pintype "bidirectional"))
      (node (ref "J8") (pin "29") (pinfunction "29_29") (pintype "bidirectional"))
      (node (ref "J9") (pin "28") (pinfunction "28_28") (pintype "bidirectional"))
      (node (ref "J9") (pin "29") (pinfunction "29_29") (pintype "bidirectional"))
    )
  )
)
